# teensy_robotica.net
KiCad netlist of a schematic drawn in EAGLE
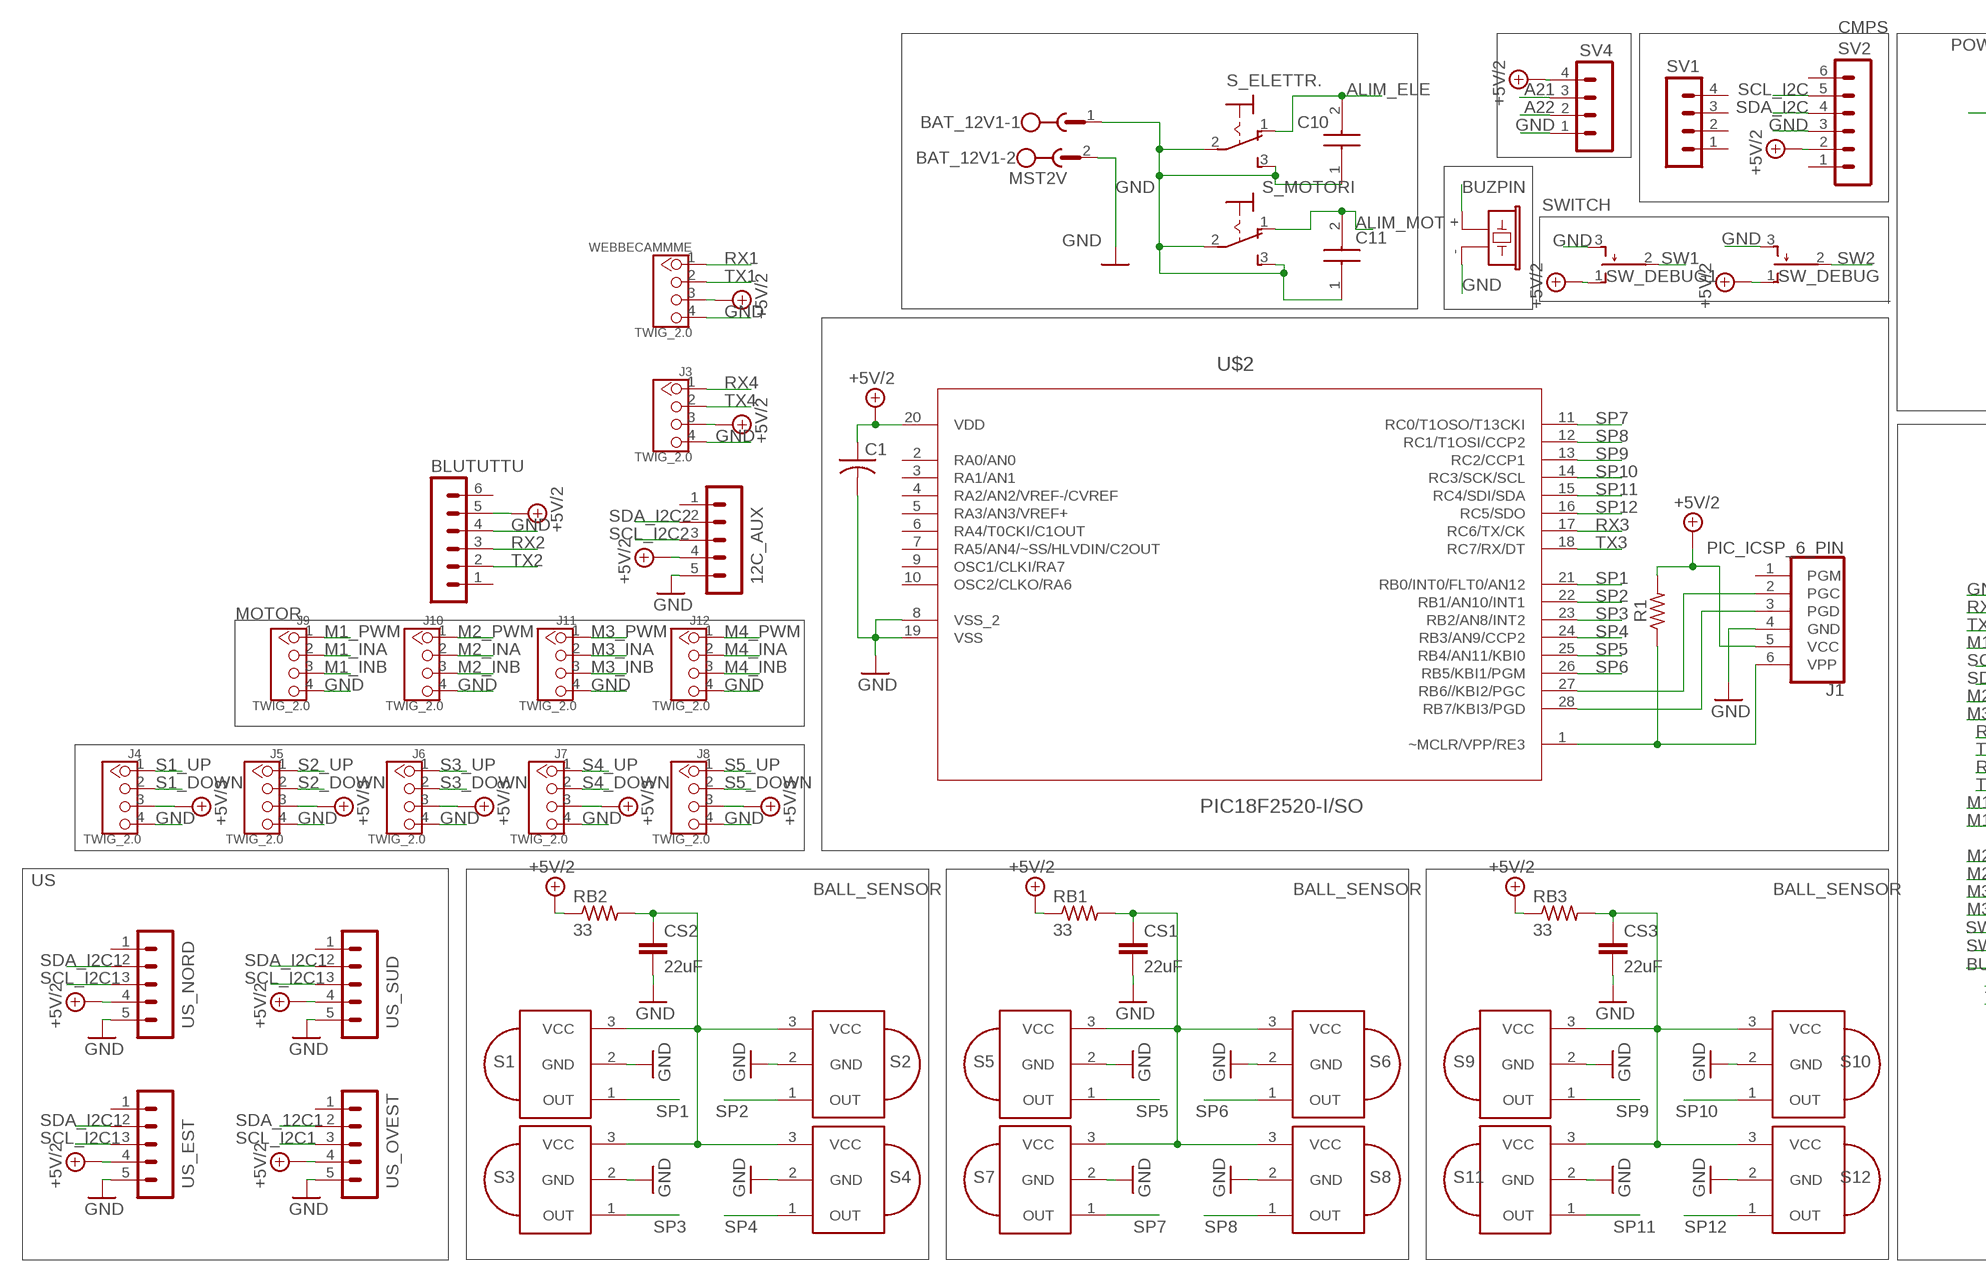
[diagram p0: schematic, sheet 1, part 1 of 2]
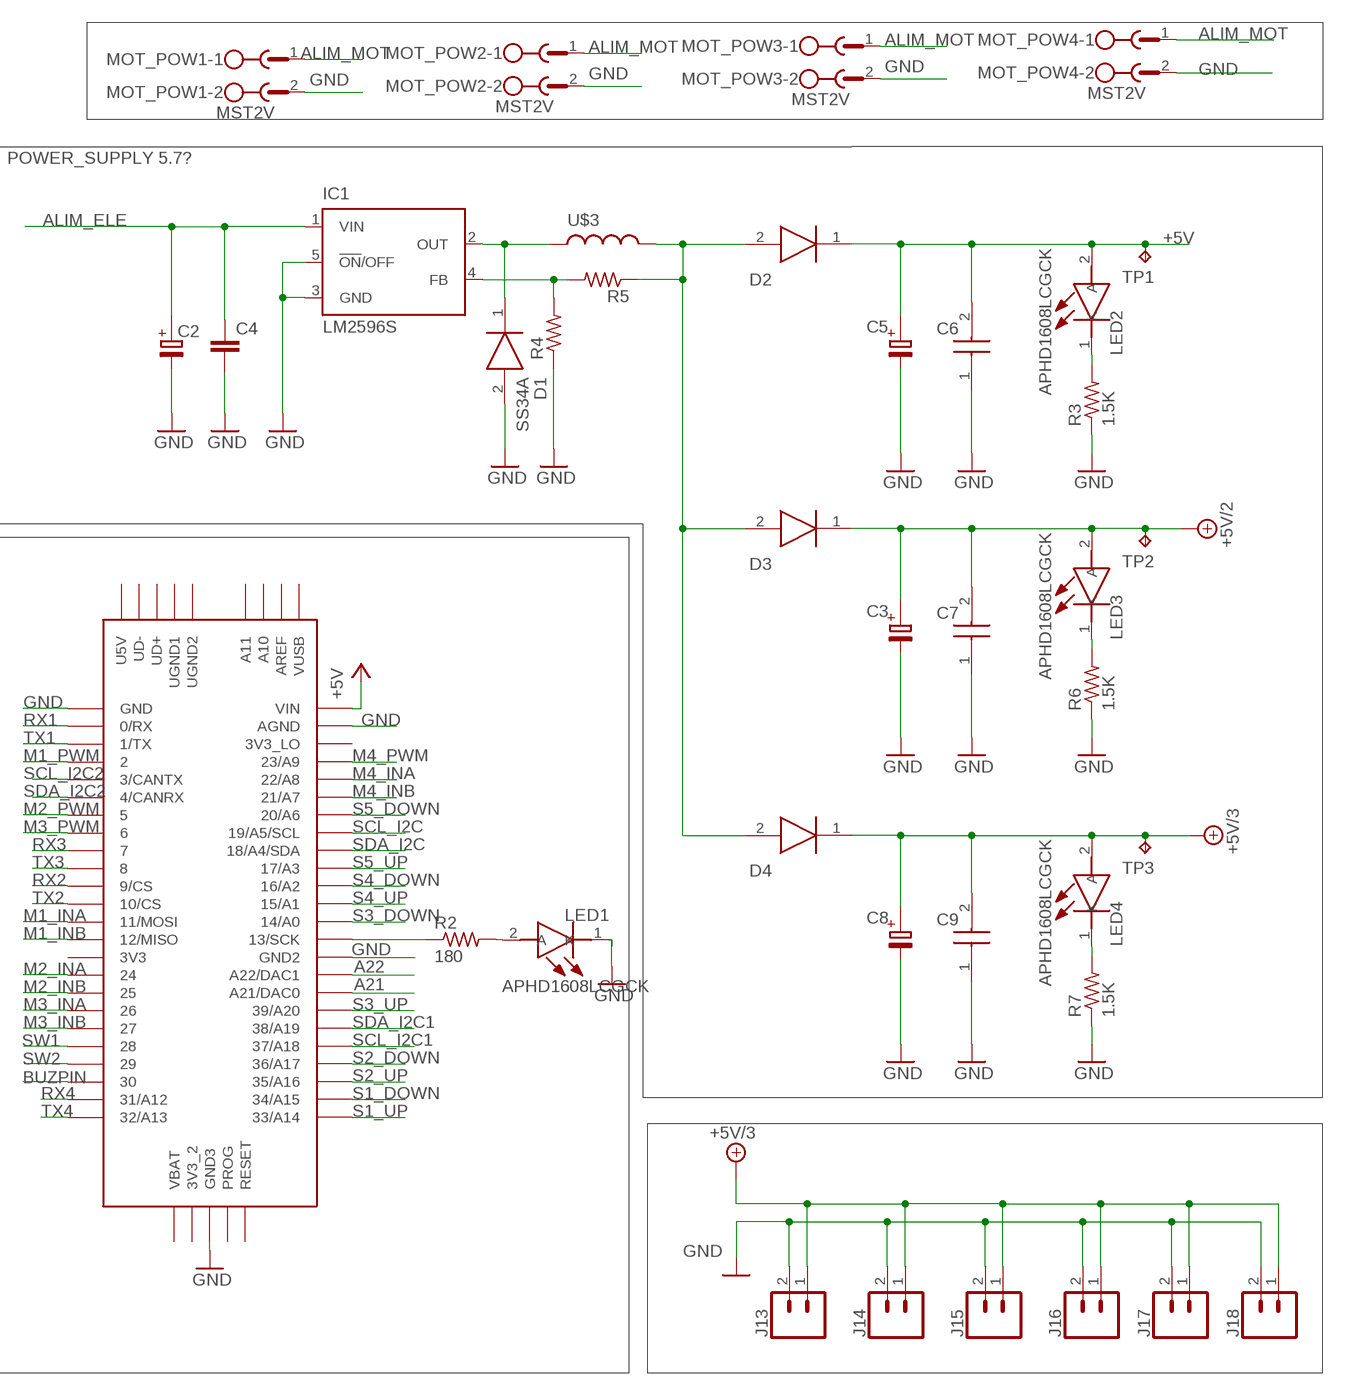
[diagram p1: schematic, sheet 1, part 2 of 2]

(export (version "E")
  (design (tool "Eeschema 10.0.6"))
  (components
    (comp (ref "12C_AUX")
      (value "MA05-1")
      (footprint "eagle-import:MA05-1")
      (libsource (lib "eagle-import") (part "MA05-1"))
    )
    (comp (ref "BAT_12V1")
      (value "MST2V")
      (footprint "eagle-import:MSTBV2")
      (libsource (lib "eagle-import") (part "MST2V"))
    )
    (comp (ref "BLUTUTTU")
      (value "MA06-1")
      (footprint "eagle-import:MA06-1")
      (libsource (lib "eagle-import") (part "MA06-1"))
    )
    (comp (ref "C1")
      (value "C-USC1206")
      (footprint "eagle-import:C1206")
      (libsource (lib "eagle-import") (part "C-USC1206"))
    )
    (comp (ref "C2")
      (value "C-PR-SMD-SV-E/F")
      (footprint "eagle-import:SV-E_F")
      (libsource (lib "eagle-import") (part "C-PR-SMD-SV-E/F"))
    )
    (comp (ref "C3")
      (value "C-PR-SMD-SV-E/F")
      (footprint "eagle-import:SV-E_F")
      (libsource (lib "eagle-import") (part "C-PR-SMD-SV-E/F"))
    )
    (comp (ref "C4")
      (value "CC1206")
      (footprint "eagle-import:C1206")
      (libsource (lib "eagle-import") (part "CC1206"))
    )
    (comp (ref "C5")
      (value "C-PR-SMD-SV-E/F")
      (footprint "eagle-import:SV-E_F")
      (libsource (lib "eagle-import") (part "C-PR-SMD-SV-E/F"))
    )
    (comp (ref "C6")
      (value "12065D106KAT2A")
      (footprint "eagle-import:CAPC3216X229N")
      (libsource (lib "eagle-import") (part "12065D106KAT2A"))
    )
    (comp (ref "C7")
      (value "12065D106KAT2A")
      (footprint "eagle-import:CAPC3216X229N")
      (libsource (lib "eagle-import") (part "12065D106KAT2A"))
    )
    (comp (ref "C8")
      (value "C-PR-SMD-SV-E/F")
      (footprint "eagle-import:SV-E_F")
      (libsource (lib "eagle-import") (part "C-PR-SMD-SV-E/F"))
    )
    (comp (ref "C9")
      (value "12065D106KAT2A")
      (footprint "eagle-import:CAPC3216X229N")
      (libsource (lib "eagle-import") (part "12065D106KAT2A"))
    )
    (comp (ref "C10")
      (value "12065D106KAT2A")
      (footprint "eagle-import:CAPC3216X229N")
      (libsource (lib "eagle-import") (part "12065D106KAT2A"))
    )
    (comp (ref "C11")
      (value "12065D106KAT2A")
      (footprint "eagle-import:CAPC3216X229N")
      (libsource (lib "eagle-import") (part "12065D106KAT2A"))
    )
    (comp (ref "CS1")
      (value "22uF")
      (footprint "eagle-import:C1206")
      (libsource (lib "eagle-import") (part "C-EUC1206"))
    )
    (comp (ref "CS2")
      (value "22uF")
      (footprint "eagle-import:C1206")
      (libsource (lib "eagle-import") (part "C-EUC1206"))
    )
    (comp (ref "CS3")
      (value "22uF")
      (footprint "eagle-import:C1206")
      (libsource (lib "eagle-import") (part "C-EUC1206"))
    )
    (comp (ref "D1")
      (value "SS34A")
      (footprint "eagle-import:DIOM5026X262N")
      (fields (field (name "RS_PART_NUMBER") "1711454"))
      (libsource (lib "eagle-import") (part "SS34A"))
    )
    (comp (ref "D2")
      (value "SE20FG-M3_H")
      (footprint "eagle-import:SODFL3718X108N")
      (fields
        (field (name "MANUFACTURER_PART_NUMBER") "SE20FG-M3/H")
        (field (name "RS_PART_NUMBER") "8949262P")
      )
      (libsource (lib "eagle-import") (part "SE20FG-M3_H"))
    )
    (comp (ref "D3")
      (value "SE20FG-M3_H")
      (footprint "eagle-import:SODFL3718X108N")
      (fields
        (field (name "MANUFACTURER_PART_NUMBER") "SE20FG-M3/H")
        (field (name "RS_PART_NUMBER") "8949262P")
      )
      (libsource (lib "eagle-import") (part "SE20FG-M3_H"))
    )
    (comp (ref "D4")
      (value "SE20FG-M3_H")
      (footprint "eagle-import:SODFL3718X108N")
      (fields
        (field (name "MANUFACTURER_PART_NUMBER") "SE20FG-M3/H")
        (field (name "RS_PART_NUMBER") "8949262P")
      )
      (libsource (lib "eagle-import") (part "SE20FG-M3_H"))
    )
    (comp (ref "IC1")
      (value "LM2596S")
      (footprint "eagle-import:TO263-5")
      (fields (field (name "MF") "NATIONAL SEMICONDUCTOR") (field (name "MPN") "LM2596S-ADJ/NOPB"))
      (libsource (lib "eagle-import") (part "LM2596S"))
    )
    (comp (ref "J1")
      (value "PIC_ICSP_6_PIN")
      (footprint "eagle-import:MOLEX-1X6")
      (libsource (lib "eagle-import") (part "PIC_ICSP_6_PIN"))
    )
    (comp (ref "J3")
      (value "TWIG_2.0")
      (footprint "eagle-import:2.0_1X4")
      (libsource (lib "eagle-import") (part "TWIG_2.0"))
    )
    (comp (ref "J4")
      (value "TWIG_2.0")
      (footprint "eagle-import:2.0_1X4")
      (libsource (lib "eagle-import") (part "TWIG_2.0"))
    )
    (comp (ref "J5")
      (value "TWIG_2.0")
      (footprint "eagle-import:2.0_1X4")
      (libsource (lib "eagle-import") (part "TWIG_2.0"))
    )
    (comp (ref "J6")
      (value "TWIG_2.0")
      (footprint "eagle-import:2.0_1X4")
      (libsource (lib "eagle-import") (part "TWIG_2.0"))
    )
    (comp (ref "J7")
      (value "TWIG_2.0")
      (footprint "eagle-import:2.0_1X4")
      (libsource (lib "eagle-import") (part "TWIG_2.0"))
    )
    (comp (ref "J8")
      (value "TWIG_2.0")
      (footprint "eagle-import:2.0_1X4")
      (libsource (lib "eagle-import") (part "TWIG_2.0"))
    )
    (comp (ref "J9")
      (value "TWIG_2.0")
      (footprint "eagle-import:2.0_1X4")
      (libsource (lib "eagle-import") (part "TWIG_2.0"))
    )
    (comp (ref "J10")
      (value "TWIG_2.0")
      (footprint "eagle-import:2.0_1X4")
      (libsource (lib "eagle-import") (part "TWIG_2.0"))
    )
    (comp (ref "J11")
      (value "TWIG_2.0")
      (footprint "eagle-import:2.0_1X4")
      (libsource (lib "eagle-import") (part "TWIG_2.0"))
    )
    (comp (ref "J12")
      (value "TWIG_2.0")
      (footprint "eagle-import:2.0_1X4")
      (libsource (lib "eagle-import") (part "TWIG_2.0"))
    )
    (comp (ref "J13")
      (value "CONN_02")
      (footprint "eagle-import:1X02")
      (libsource (lib "eagle-import") (part "CONN_02"))
    )
    (comp (ref "J14")
      (value "CONN_02")
      (footprint "eagle-import:1X02")
      (libsource (lib "eagle-import") (part "CONN_02"))
    )
    (comp (ref "J15")
      (value "CONN_02")
      (footprint "eagle-import:1X02")
      (libsource (lib "eagle-import") (part "CONN_02"))
    )
    (comp (ref "J16")
      (value "CONN_02")
      (footprint "eagle-import:1X02")
      (libsource (lib "eagle-import") (part "CONN_02"))
    )
    (comp (ref "J17")
      (value "CONN_02")
      (footprint "eagle-import:1X02")
      (libsource (lib "eagle-import") (part "CONN_02"))
    )
    (comp (ref "J18")
      (value "CONN_02")
      (footprint "eagle-import:1X02")
      (libsource (lib "eagle-import") (part "CONN_02"))
    )
    (comp (ref "LED1")
      (value "APHD1608LCGCK")
      (footprint "eagle-import:LEDM168X80N")
      (fields (field (name "MOUSER_PART_NUMBER") "604-APHD1608LCGCK"))
      (libsource (lib "eagle-import") (part "APHD1608LCGCK"))
    )
    (comp (ref "LED2")
      (value "APHD1608LCGCK")
      (footprint "eagle-import:LEDM168X80N")
      (fields (field (name "MOUSER_PART_NUMBER") "604-APHD1608LCGCK"))
      (libsource (lib "eagle-import") (part "APHD1608LCGCK"))
    )
    (comp (ref "LED3")
      (value "APHD1608LCGCK")
      (footprint "eagle-import:LEDM168X80N")
      (fields (field (name "MOUSER_PART_NUMBER") "604-APHD1608LCGCK"))
      (libsource (lib "eagle-import") (part "APHD1608LCGCK"))
    )
    (comp (ref "LED4")
      (value "APHD1608LCGCK")
      (footprint "eagle-import:LEDM168X80N")
      (fields (field (name "MOUSER_PART_NUMBER") "604-APHD1608LCGCK"))
      (libsource (lib "eagle-import") (part "APHD1608LCGCK"))
    )
    (comp (ref "MOT_POW1")
      (value "MST2V")
      (footprint "eagle-import:MSTBV2")
      (libsource (lib "eagle-import") (part "MST2V"))
    )
    (comp (ref "MOT_POW2")
      (value "MST2V")
      (footprint "eagle-import:MSTBV2")
      (libsource (lib "eagle-import") (part "MST2V"))
    )
    (comp (ref "MOT_POW3")
      (value "MST2V")
      (footprint "eagle-import:MSTBV2")
      (libsource (lib "eagle-import") (part "MST2V"))
    )
    (comp (ref "MOT_POW4")
      (value "MST2V")
      (footprint "eagle-import:MSTBV2")
      (libsource (lib "eagle-import") (part "MST2V"))
    )
    (comp (ref "R1")
      (value "10k")
      (footprint "eagle-import:M1206")
      (libsource (lib "eagle-import") (part "R-US_M1206"))
    )
    (comp (ref "R2")
      (value "180")
      (footprint "eagle-import:M1206")
      (libsource (lib "eagle-import") (part "R-US_M1206"))
    )
    (comp (ref "R3")
      (value "1.5K")
      (footprint "eagle-import:R1206")
      (libsource (lib "eagle-import") (part "R-US_R1206"))
    )
    (comp (ref "R4")
      (value "R-US_R1206")
      (footprint "eagle-import:R1206")
      (libsource (lib "eagle-import") (part "R-US_R1206"))
    )
    (comp (ref "R5")
      (value "R-US_R1206")
      (footprint "eagle-import:R1206")
      (libsource (lib "eagle-import") (part "R-US_R1206"))
    )
    (comp (ref "R6")
      (value "1.5K")
      (footprint "eagle-import:R1206")
      (libsource (lib "eagle-import") (part "R-US_R1206"))
    )
    (comp (ref "R7")
      (value "1.5K")
      (footprint "eagle-import:R1206")
      (libsource (lib "eagle-import") (part "R-US_R1206"))
    )
    (comp (ref "RB1")
      (value "33")
      (footprint "eagle-import:M1206")
      (libsource (lib "eagle-import") (part "R-US_M1206"))
    )
    (comp (ref "RB2")
      (value "33")
      (footprint "eagle-import:M1206")
      (libsource (lib "eagle-import") (part "R-US_M1206"))
    )
    (comp (ref "RB3")
      (value "33")
      (footprint "eagle-import:M1206")
      (libsource (lib "eagle-import") (part "R-US_M1206"))
    )
    (comp (ref "S1")
      (value "PNA460XM")
      (footprint "eagle-import:PNA460XM")
      (libsource (lib "eagle-import") (part "PNA460XM"))
    )
    (comp (ref "S2")
      (value "PNA460XM")
      (footprint "eagle-import:PNA460XM")
      (libsource (lib "eagle-import") (part "PNA460XM"))
    )
    (comp (ref "S3")
      (value "PNA460XM")
      (footprint "eagle-import:PNA460XM")
      (libsource (lib "eagle-import") (part "PNA460XM"))
    )
    (comp (ref "S4")
      (value "PNA460XM")
      (footprint "eagle-import:PNA460XM")
      (libsource (lib "eagle-import") (part "PNA460XM"))
    )
    (comp (ref "S5")
      (value "PNA460XM")
      (footprint "eagle-import:PNA460XM")
      (libsource (lib "eagle-import") (part "PNA460XM"))
    )
    (comp (ref "S6")
      (value "PNA460XM")
      (footprint "eagle-import:PNA460XM")
      (libsource (lib "eagle-import") (part "PNA460XM"))
    )
    (comp (ref "S7")
      (value "PNA460XM")
      (footprint "eagle-import:PNA460XM")
      (libsource (lib "eagle-import") (part "PNA460XM"))
    )
    (comp (ref "S8")
      (value "PNA460XM")
      (footprint "eagle-import:PNA460XM")
      (libsource (lib "eagle-import") (part "PNA460XM"))
    )
    (comp (ref "S9")
      (value "PNA460XM")
      (footprint "eagle-import:PNA460XM")
      (libsource (lib "eagle-import") (part "PNA460XM"))
    )
    (comp (ref "S10")
      (value "PNA460XM")
      (footprint "eagle-import:PNA460XM")
      (libsource (lib "eagle-import") (part "PNA460XM"))
    )
    (comp (ref "S11")
      (value "PNA460XM")
      (footprint "eagle-import:PNA460XM")
      (libsource (lib "eagle-import") (part "PNA460XM"))
    )
    (comp (ref "S12")
      (value "PNA460XM")
      (footprint "eagle-import:PNA460XM")
      (libsource (lib "eagle-import") (part "PNA460XM"))
    )
    (comp (ref "SG1")
      (value "F/CM12P")
      (footprint "eagle-import:F_CM12P")
      (libsource (lib "eagle-import") (part "F/CM12P"))
    )
    (comp (ref "SV1")
      (value "MA04-1")
      (footprint "eagle-import:MA04-1")
      (libsource (lib "eagle-import") (part "MA04-1"))
    )
    (comp (ref "SV2")
      (value "MA06-1")
      (footprint "eagle-import:MA06-1")
      (libsource (lib "eagle-import") (part "MA06-1"))
    )
    (comp (ref "SV4")
      (value "MA04-1")
      (footprint "eagle-import:MA04-1")
      (libsource (lib "eagle-import") (part "MA04-1"))
    )
    (comp (ref "SW_DEBUG")
      (value "TL38PO")
      (footprint "eagle-import:TL3XPO")
      (libsource (lib "eagle-import") (part "TL38PO"))
    )
    (comp (ref "SW_DEBUG1")
      (value "TL38PO")
      (footprint "eagle-import:TL3XPO")
      (libsource (lib "eagle-import") (part "TL38PO"))
    )
    (comp (ref "S_ELETTR.")
      (value "320-916")
      (footprint "eagle-import:320-916")
      (libsource (lib "eagle-import") (part "320-916"))
    )
    (comp (ref "S_MOTORI")
      (value "320-916")
      (footprint "eagle-import:320-916")
      (libsource (lib "eagle-import") (part "320-916"))
    )
    (comp (ref "TP1")
      (value "TPTP13SQ")
      (footprint "eagle-import:TP13SQ")
      (libsource (lib "eagle-import") (part "TPTP13SQ"))
    )
    (comp (ref "TP2")
      (value "TPTP13SQ")
      (footprint "eagle-import:TP13SQ")
      (libsource (lib "eagle-import") (part "TPTP13SQ"))
    )
    (comp (ref "TP3")
      (value "TPTP13SQ")
      (footprint "eagle-import:TP13SQ")
      (libsource (lib "eagle-import") (part "TPTP13SQ"))
    )
    (comp (ref "U$1")
      (value "TEENSY_3.5/3.6")
      (footprint "eagle-import:TEENSY_3.5_3.6")
      (libsource (lib "eagle-import") (part "TEENSY_3.5/3.6"))
    )
    (comp (ref "U$2")
      (value "PIC18F2520-I/SO")
      (footprint "eagle-import:SOIC127P1030X265-28N")
      (libsource (lib "eagle-import") (part "PIC18F2520-I/SO"))
    )
    (comp (ref "U$3")
      (value "MSS1260")
      (footprint "eagle-import:MSS1260")
      (libsource (lib "eagle-import") (part "MSS1260"))
    )
    (comp (ref "US_EST")
      (value "MA05-1")
      (footprint "eagle-import:MA05-1")
      (libsource (lib "eagle-import") (part "MA05-1"))
    )
    (comp (ref "US_NORD")
      (value "MA05-1")
      (footprint "eagle-import:MA05-1")
      (libsource (lib "eagle-import") (part "MA05-1"))
    )
    (comp (ref "US_OVEST")
      (value "MA05-1")
      (footprint "eagle-import:MA05-1")
      (libsource (lib "eagle-import") (part "MA05-1"))
    )
    (comp (ref "US_SUD")
      (value "MA05-1")
      (footprint "eagle-import:MA05-1")
      (libsource (lib "eagle-import") (part "MA05-1"))
    )
    (comp (ref "WEBBECAMMME")
      (value "TWIG_2.0")
      (footprint "eagle-import:2.0_1X4")
      (libsource (lib "eagle-import") (part "TWIG_2.0"))
    )
  )
  (nets
    (net (code "1") (name "+5V") (class "Default")
      (node (ref "C5") (pin "+") (pinfunction "+_+") (pintype "passive"))
      (node (ref "C6") (pin "2") (pinfunction "2_2") (pintype "bidirectional"))
      (node (ref "D2") (pin "1") (pinfunction "K_1") (pintype "bidirectional"))
      (node (ref "LED2") (pin "2") (pinfunction "A_2") (pintype "bidirectional"))
      (node (ref "TP1") (pin "TP") (pinfunction "TP_TP") (pintype "input"))
      (node (ref "U$1") (pin "VIN") (pinfunction "VIN_VIN") (pintype "bidirectional"))
    )
    (net (code "2") (name "+5V{slash}2") (class "Default")
      (node (ref "12C_AUX") (pin "4") (pinfunction "4_4") (pintype "passive"))
      (node (ref "BLUTUTTU") (pin "5") (pinfunction "5_5") (pintype "passive"))
      (node (ref "C1") (pin "1") (pinfunction "1_1") (pintype "passive"))
      (node (ref "C3") (pin "+") (pinfunction "+_+") (pintype "passive"))
      (node (ref "C7") (pin "2") (pinfunction "2_2") (pintype "bidirectional"))
      (node (ref "D3") (pin "1") (pinfunction "K_1") (pintype "bidirectional"))
      (node (ref "J1") (pin "5") (pinfunction "VCC_5") (pintype "power_in"))
      (node (ref "J3") (pin "3") (pinfunction "3_3") (pintype "bidirectional"))
      (node (ref "LED3") (pin "2") (pinfunction "A_2") (pintype "bidirectional"))
      (node (ref "R1") (pin "2") (pinfunction "2_2") (pintype "passive"))
      (node (ref "RB1") (pin "1") (pinfunction "1_1") (pintype "passive"))
      (node (ref "RB2") (pin "1") (pinfunction "1_1") (pintype "passive"))
      (node (ref "RB3") (pin "1") (pinfunction "1_1") (pintype "passive"))
      (node (ref "SV2") (pin "2") (pinfunction "2_2") (pintype "passive"))
      (node (ref "SV4") (pin "4") (pinfunction "4_4") (pintype "passive"))
      (node (ref "SW_DEBUG") (pin "1") (pinfunction "O_1") (pintype "passive"))
      (node (ref "SW_DEBUG1") (pin "1") (pinfunction "O_1") (pintype "passive"))
      (node (ref "TP2") (pin "TP") (pinfunction "TP_TP") (pintype "input"))
      (node (ref "U$2") (pin "20") (pinfunction "VDD_20") (pintype "bidirectional"))
      (node (ref "US_EST") (pin "4") (pinfunction "4_4") (pintype "passive"))
      (node (ref "US_NORD") (pin "4") (pinfunction "4_4") (pintype "passive"))
      (node (ref "US_OVEST") (pin "4") (pinfunction "4_4") (pintype "passive"))
      (node (ref "US_SUD") (pin "4") (pinfunction "4_4") (pintype "passive"))
      (node (ref "WEBBECAMMME") (pin "3") (pinfunction "3_3") (pintype "bidirectional"))
    )
    (net (code "3") (name "+5V{slash}3") (class "Default")
      (node (ref "C8") (pin "+") (pinfunction "+_+") (pintype "passive"))
      (node (ref "C9") (pin "2") (pinfunction "2_2") (pintype "bidirectional"))
      (node (ref "D4") (pin "1") (pinfunction "K_1") (pintype "bidirectional"))
      (node (ref "J13") (pin "1") (pinfunction "1_1") (pintype "passive"))
      (node (ref "J14") (pin "1") (pinfunction "1_1") (pintype "passive"))
      (node (ref "J15") (pin "1") (pinfunction "1_1") (pintype "passive"))
      (node (ref "J16") (pin "1") (pinfunction "1_1") (pintype "passive"))
      (node (ref "J17") (pin "1") (pinfunction "1_1") (pintype "passive"))
      (node (ref "J18") (pin "1") (pinfunction "1_1") (pintype "passive"))
      (node (ref "J4") (pin "3") (pinfunction "3_3") (pintype "bidirectional"))
      (node (ref "J5") (pin "3") (pinfunction "3_3") (pintype "bidirectional"))
      (node (ref "J6") (pin "3") (pinfunction "3_3") (pintype "bidirectional"))
      (node (ref "J7") (pin "3") (pinfunction "3_3") (pintype "bidirectional"))
      (node (ref "J8") (pin "3") (pinfunction "3_3") (pintype "bidirectional"))
      (node (ref "LED4") (pin "2") (pinfunction "A_2") (pintype "bidirectional"))
      (node (ref "TP3") (pin "TP") (pinfunction "TP_TP") (pintype "input"))
    )
    (net (code "4") (name "/A21") (class "Default")
      (node (ref "SV4") (pin "3") (pinfunction "3_3") (pintype "passive"))
      (node (ref "U$1") (pin "21/DAC0") (pinfunction "A21/DAC0_21/DAC0") (pintype "bidirectional"))
    )
    (net (code "5") (name "/A22") (class "Default")
      (node (ref "SV4") (pin "2") (pinfunction "2_2") (pintype "passive"))
      (node (ref "U$1") (pin "A22/DAC1") (pinfunction "A22/DAC1_A22/DAC1") (pintype "bidirectional"))
    )
    (net (code "6") (name "/ALIM_ELE") (class "Default")
      (node (ref "C10") (pin "2") (pinfunction "2_2") (pintype "bidirectional"))
      (node (ref "C2") (pin "+") (pinfunction "+_+") (pintype "passive"))
      (node (ref "C4") (pin "1") (pinfunction "1_1") (pintype "passive"))
      (node (ref "IC1") (pin "1") (pinfunction "VIN_1") (pintype "input"))
      (node (ref "S_ELETTR.") (pin "1") (pinfunction "O_1") (pintype "passive"))
    )
    (net (code "7") (name "/ALIM_MOT") (class "Default")
      (node (ref "C11") (pin "2") (pinfunction "2_2") (pintype "bidirectional"))
      (node (ref "MOT_POW1") (pin "1") (pinfunction "1_1") (pintype "passive"))
      (node (ref "MOT_POW2") (pin "1") (pinfunction "1_1") (pintype "passive"))
      (node (ref "MOT_POW3") (pin "1") (pinfunction "1_1") (pintype "passive"))
      (node (ref "MOT_POW4") (pin "1") (pinfunction "1_1") (pintype "passive"))
      (node (ref "S_MOTORI") (pin "1") (pinfunction "O_1") (pintype "passive"))
    )
    (net (code "8") (name "/BUZPIN") (class "Default")
      (node (ref "SG1") (pin "+") (pinfunction "1_+") (pintype "passive"))
      (node (ref "U$1") (pin "30") (pinfunction "30_30") (pintype "bidirectional"))
    )
    (net (code "9") (name "/M1_INA") (class "Default")
      (node (ref "J9") (pin "2") (pinfunction "2_2") (pintype "bidirectional"))
      (node (ref "U$1") (pin "11/MOSI") (pinfunction "11/MOSI_11/MOSI") (pintype "bidirectional"))
    )
    (net (code "10") (name "/M1_INB") (class "Default")
      (node (ref "J9") (pin "3") (pinfunction "3_3") (pintype "bidirectional"))
      (node (ref "U$1") (pin "12/MISO") (pinfunction "12/MISO_12/MISO") (pintype "bidirectional"))
    )
    (net (code "11") (name "/M1_PWM") (class "Default")
      (node (ref "J9") (pin "1") (pinfunction "1_1") (pintype "bidirectional"))
      (node (ref "U$1") (pin "2") (pinfunction "2_2") (pintype "bidirectional"))
    )
    (net (code "12") (name "/M2_INA") (class "Default")
      (node (ref "J10") (pin "2") (pinfunction "2_2") (pintype "bidirectional"))
      (node (ref "U$1") (pin "24") (pinfunction "24_24") (pintype "bidirectional"))
    )
    (net (code "13") (name "/M2_INB") (class "Default")
      (node (ref "J10") (pin "3") (pinfunction "3_3") (pintype "bidirectional"))
      (node (ref "U$1") (pin "25") (pinfunction "25_25") (pintype "bidirectional"))
    )
    (net (code "14") (name "/M2_PWM") (class "Default")
      (node (ref "J10") (pin "1") (pinfunction "1_1") (pintype "bidirectional"))
      (node (ref "U$1") (pin "5") (pinfunction "5_5") (pintype "bidirectional"))
    )
    (net (code "15") (name "/M3_INA") (class "Default")
      (node (ref "J11") (pin "2") (pinfunction "2_2") (pintype "bidirectional"))
      (node (ref "U$1") (pin "26") (pinfunction "26_26") (pintype "bidirectional"))
    )
    (net (code "16") (name "/M3_INB") (class "Default")
      (node (ref "J11") (pin "3") (pinfunction "3_3") (pintype "bidirectional"))
      (node (ref "U$1") (pin "27") (pinfunction "27_27") (pintype "bidirectional"))
    )
    (net (code "17") (name "/M3_PWM") (class "Default")
      (node (ref "J11") (pin "1") (pinfunction "1_1") (pintype "bidirectional"))
      (node (ref "U$1") (pin "6") (pinfunction "6_6") (pintype "bidirectional"))
    )
    (net (code "18") (name "/M4_INA") (class "Default")
      (node (ref "J12") (pin "2") (pinfunction "2_2") (pintype "bidirectional"))
      (node (ref "U$1") (pin "22/A8") (pinfunction "22/A8_22/A8") (pintype "bidirectional"))
    )
    (net (code "19") (name "/M4_INB") (class "Default")
      (node (ref "J12") (pin "3") (pinfunction "3_3") (pintype "bidirectional"))
      (node (ref "U$1") (pin "21/A7") (pinfunction "21/A7_21/A7") (pintype "bidirectional"))
    )
    (net (code "20") (name "/M4_PWM") (class "Default")
      (node (ref "J12") (pin "1") (pinfunction "1_1") (pintype "bidirectional"))
      (node (ref "U$1") (pin "23/A9") (pinfunction "23/A9_23/A9") (pintype "bidirectional"))
    )
    (net (code "21") (name "/RX1") (class "Default")
      (node (ref "U$1") (pin "0/RX") (pinfunction "0/RX_0/RX") (pintype "bidirectional"))
      (node (ref "WEBBECAMMME") (pin "1") (pinfunction "1_1") (pintype "bidirectional"))
    )
    (net (code "22") (name "/RX2") (class "Default")
      (node (ref "BLUTUTTU") (pin "3") (pinfunction "3_3") (pintype "passive"))
      (node (ref "U$1") (pin "9/CS") (pinfunction "9/CS_9/CS") (pintype "bidirectional"))
    )
    (net (code "23") (name "/RX3") (class "Default")
      (node (ref "U$1") (pin "7") (pinfunction "7_7") (pintype "bidirectional"))
      (node (ref "U$2") (pin "17") (pinfunction "RC6/TX/CK_17") (pintype "bidirectional"))
    )
    (net (code "24") (name "/RX4") (class "Default")
      (node (ref "J3") (pin "1") (pinfunction "1_1") (pintype "bidirectional"))
      (node (ref "U$1") (pin "31/A12") (pinfunction "31/A12_31/A12") (pintype "bidirectional"))
    )
    (net (code "25") (name "/S1_DOWN") (class "Default")
      (node (ref "J4") (pin "2") (pinfunction "2_2") (pintype "bidirectional"))
      (node (ref "U$1") (pin "34/A15") (pinfunction "34/A15_34/A15") (pintype "bidirectional"))
    )
    (net (code "26") (name "/S1_UP") (class "Default")
      (node (ref "J4") (pin "1") (pinfunction "1_1") (pintype "bidirectional"))
      (node (ref "U$1") (pin "33/A14") (pinfunction "33/A14_33/A14") (pintype "bidirectional"))
    )
    (net (code "27") (name "/S2_DOWN") (class "Default")
      (node (ref "J5") (pin "2") (pinfunction "2_2") (pintype "bidirectional"))
      (node (ref "U$1") (pin "36/A17") (pinfunction "36/A17_36/A17") (pintype "bidirectional"))
    )
    (net (code "28") (name "/S2_UP") (class "Default")
      (node (ref "J5") (pin "1") (pinfunction "1_1") (pintype "bidirectional"))
      (node (ref "U$1") (pin "35/A16") (pinfunction "35/A16_35/A16") (pintype "bidirectional"))
    )
    (net (code "29") (name "/S3_DOWN") (class "Default")
      (node (ref "J6") (pin "2") (pinfunction "2_2") (pintype "bidirectional"))
      (node (ref "U$1") (pin "14/A0") (pinfunction "14/A0_14/A0") (pintype "bidirectional"))
    )
    (net (code "30") (name "/S3_UP") (class "Default")
      (node (ref "J6") (pin "1") (pinfunction "1_1") (pintype "bidirectional"))
      (node (ref "U$1") (pin "39/A20") (pinfunction "39/A20_39/A20") (pintype "bidirectional"))
    )
    (net (code "31") (name "/S4_DOWN") (class "Default")
      (node (ref "J7") (pin "2") (pinfunction "2_2") (pintype "bidirectional"))
      (node (ref "U$1") (pin "16/A2") (pinfunction "16/A2_16/A2") (pintype "bidirectional"))
    )
    (net (code "32") (name "/S4_UP") (class "Default")
      (node (ref "J7") (pin "1") (pinfunction "1_1") (pintype "bidirectional"))
      (node (ref "U$1") (pin "15/A1") (pinfunction "15/A1_15/A1") (pintype "bidirectional"))
    )
    (net (code "33") (name "/S5_DOWN") (class "Default")
      (node (ref "J8") (pin "2") (pinfunction "2_2") (pintype "bidirectional"))
      (node (ref "U$1") (pin "20/A6") (pinfunction "20/A6_20/A6") (pintype "bidirectional"))
    )
    (net (code "34") (name "/S5_UP") (class "Default")
      (node (ref "J8") (pin "1") (pinfunction "1_1") (pintype "bidirectional"))
      (node (ref "U$1") (pin "17/A3") (pinfunction "17/A3_17/A3") (pintype "bidirectional"))
    )
    (net (code "35") (name "/SCL_I2C") (class "Default")
      (node (ref "SV2") (pin "5") (pinfunction "5_5") (pintype "passive"))
      (node (ref "U$1") (pin "19/A5/SCL") (pinfunction "19/A5/SCL_19/A5/SCL") (pintype "bidirectional"))
    )
    (net (code "36") (name "/SCL_I2C1") (class "Default")
      (node (ref "U$1") (pin "37/A18") (pinfunction "37/A18_37/A18") (pintype "bidirectional"))
      (node (ref "US_EST") (pin "3") (pinfunction "3_3") (pintype "passive"))
      (node (ref "US_NORD") (pin "3") (pinfunction "3_3") (pintype "passive"))
      (node (ref "US_OVEST") (pin "3") (pinfunction "3_3") (pintype "passive"))
      (node (ref "US_SUD") (pin "3") (pinfunction "3_3") (pintype "passive"))
    )
    (net (code "37") (name "/SCL_I2C2") (class "Default")
      (node (ref "12C_AUX") (pin "3") (pinfunction "3_3") (pintype "passive"))
      (node (ref "U$1") (pin "3/CANTX") (pinfunction "3/CANTX_3/CANTX") (pintype "bidirectional"))
    )
    (net (code "38") (name "/SDA_12C1") (class "Default")
      (node (ref "US_OVEST") (pin "2") (pinfunction "2_2") (pintype "passive"))
    )
    (net (code "39") (name "/SDA_I2C") (class "Default")
      (node (ref "SV2") (pin "4") (pinfunction "4_4") (pintype "passive"))
      (node (ref "U$1") (pin "18/A4/SDA") (pinfunction "18/A4/SDA_18/A4/SDA") (pintype "bidirectional"))
    )
    (net (code "40") (name "/SDA_I2C1") (class "Default")
      (node (ref "U$1") (pin "38/A19") (pinfunction "38/A19_38/A19") (pintype "bidirectional"))
      (node (ref "US_EST") (pin "2") (pinfunction "2_2") (pintype "passive"))
      (node (ref "US_NORD") (pin "2") (pinfunction "2_2") (pintype "passive"))
      (node (ref "US_SUD") (pin "2") (pinfunction "2_2") (pintype "passive"))
    )
    (net (code "41") (name "/SDA_I2C2") (class "Default")
      (node (ref "12C_AUX") (pin "2") (pinfunction "2_2") (pintype "passive"))
      (node (ref "U$1") (pin "4/CANRX") (pinfunction "4/CANRX_4/CANRX") (pintype "bidirectional"))
    )
    (net (code "42") (name "/SP1") (class "Default")
      (node (ref "S1") (pin "1") (pinfunction "OUT_1") (pintype "output"))
      (node (ref "U$2") (pin "21") (pinfunction "RB0/INT0/FLT0/AN12_21") (pintype "bidirectional"))
    )
    (net (code "43") (name "/SP2") (class "Default")
      (node (ref "S2") (pin "1") (pinfunction "OUT_1") (pintype "output"))
      (node (ref "U$2") (pin "22") (pinfunction "RB1/AN10/INT1_22") (pintype "bidirectional"))
    )
    (net (code "44") (name "/SP3") (class "Default")
      (node (ref "S3") (pin "1") (pinfunction "OUT_1") (pintype "output"))
      (node (ref "U$2") (pin "23") (pinfunction "RB2/AN8/INT2_23") (pintype "bidirectional"))
    )
    (net (code "45") (name "/SP4") (class "Default")
      (node (ref "S4") (pin "1") (pinfunction "OUT_1") (pintype "output"))
      (node (ref "U$2") (pin "24") (pinfunction "RB3/AN9/CCP2_24") (pintype "bidirectional"))
    )
    (net (code "46") (name "/SP5") (class "Default")
      (node (ref "S5") (pin "1") (pinfunction "OUT_1") (pintype "output"))
      (node (ref "U$2") (pin "25") (pinfunction "RB4/AN11/KBI0_25") (pintype "bidirectional"))
    )
    (net (code "47") (name "/SP6") (class "Default")
      (node (ref "S6") (pin "1") (pinfunction "OUT_1") (pintype "output"))
      (node (ref "U$2") (pin "26") (pinfunction "RB5/KBI1/PGM_26") (pintype "bidirectional"))
    )
    (net (code "48") (name "/SP7") (class "Default")
      (node (ref "S7") (pin "1") (pinfunction "OUT_1") (pintype "output"))
      (node (ref "U$2") (pin "11") (pinfunction "RC0/T1OSO/T13CKI_11") (pintype "bidirectional"))
    )
    (net (code "49") (name "/SP8") (class "Default")
      (node (ref "S8") (pin "1") (pinfunction "OUT_1") (pintype "output"))
      (node (ref "U$2") (pin "12") (pinfunction "RC1/T1OSI/CCP2_12") (pintype "bidirectional"))
    )
    (net (code "50") (name "/SP9") (class "Default")
      (node (ref "S9") (pin "1") (pinfunction "OUT_1") (pintype "output"))
      (node (ref "U$2") (pin "13") (pinfunction "RC2/CCP1_13") (pintype "bidirectional"))
    )
    (net (code "51") (name "/SP10") (class "Default")
      (node (ref "S10") (pin "1") (pinfunction "OUT_1") (pintype "output"))
      (node (ref "U$2") (pin "14") (pinfunction "RC3/SCK/SCL_14") (pintype "bidirectional"))
    )
    (net (code "52") (name "/SP11") (class "Default")
      (node (ref "S11") (pin "1") (pinfunction "OUT_1") (pintype "output"))
      (node (ref "U$2") (pin "15") (pinfunction "RC4/SDI/SDA_15") (pintype "bidirectional"))
    )
    (net (code "53") (name "/SP12") (class "Default")
      (node (ref "S12") (pin "1") (pinfunction "OUT_1") (pintype "output"))
      (node (ref "U$2") (pin "16") (pinfunction "RC5/SDO_16") (pintype "bidirectional"))
    )
    (net (code "54") (name "/SW1") (class "Default")
      (node (ref "SW_DEBUG1") (pin "2") (pinfunction "P_2") (pintype "passive"))
      (node (ref "U$1") (pin "28") (pinfunction "28_28") (pintype "bidirectional"))
    )
    (net (code "55") (name "/SW2") (class "Default")
      (node (ref "SW_DEBUG") (pin "2") (pinfunction "P_2") (pintype "passive"))
      (node (ref "U$1") (pin "29") (pinfunction "29_29") (pintype "bidirectional"))
    )
    (net (code "56") (name "/TX1") (class "Default")
      (node (ref "U$1") (pin "1/TX") (pinfunction "1/TX_1/TX") (pintype "bidirectional"))
      (node (ref "WEBBECAMMME") (pin "2") (pinfunction "2_2") (pintype "bidirectional"))
    )
    (net (code "57") (name "/TX2") (class "Default")
      (node (ref "BLUTUTTU") (pin "2") (pinfunction "2_2") (pintype "passive"))
      (node (ref "U$1") (pin "10/CS") (pinfunction "10/CS_10/CS") (pintype "bidirectional"))
    )
    (net (code "58") (name "/TX3") (class "Default")
      (node (ref "U$1") (pin "8") (pinfunction "8_8") (pintype "bidirectional"))
      (node (ref "U$2") (pin "18") (pinfunction "RC7/RX/DT_18") (pintype "bidirectional"))
    )
    (net (code "59") (name "/TX4") (class "Default")
      (node (ref "J3") (pin "2") (pinfunction "2_2") (pintype "bidirectional"))
      (node (ref "U$1") (pin "32/A13") (pinfunction "32/A13_32/A13") (pintype "bidirectional"))
    )
    (net (code "60") (name "GND") (class "Default")
      (node (ref "12C_AUX") (pin "5") (pinfunction "5_5") (pintype "passive"))
      (node (ref "BAT_12V1") (pin "2") (pinfunction "1_2") (pintype "passive"))
      (node (ref "BLUTUTTU") (pin "4") (pinfunction "4_4") (pintype "passive"))
      (node (ref "C1") (pin "2") (pinfunction "2_2") (pintype "passive"))
      (node (ref "C2") (pin "-") (pinfunction "-_-") (pintype "passive"))
      (node (ref "C3") (pin "-") (pinfunction "-_-") (pintype "passive"))
      (node (ref "C4") (pin "2") (pinfunction "2_2") (pintype "passive"))
      (node (ref "C5") (pin "-") (pinfunction "-_-") (pintype "passive"))
      (node (ref "C6") (pin "1") (pinfunction "1_1") (pintype "bidirectional"))
      (node (ref "C7") (pin "1") (pinfunction "1_1") (pintype "bidirectional"))
      (node (ref "C8") (pin "-") (pinfunction "-_-") (pintype "passive"))
      (node (ref "C9") (pin "1") (pinfunction "1_1") (pintype "bidirectional"))
      (node (ref "CS1") (pin "2") (pinfunction "2_2") (pintype "passive"))
      (node (ref "CS2") (pin "2") (pinfunction "2_2") (pintype "passive"))
      (node (ref "CS3") (pin "2") (pinfunction "2_2") (pintype "passive"))
      (node (ref "D1") (pin "2") (pinfunction "A_2") (pintype "bidirectional"))
      (node (ref "IC1") (pin "3") (pinfunction "GND_3") (pintype "power_in"))
      (node (ref "IC1") (pin "5") (pinfunction "~{ON}/OFF_5") (pintype "input"))
      (node (ref "J1") (pin "4") (pinfunction "GND_4") (pintype "power_in"))
      (node (ref "J10") (pin "4") (pinfunction "4_4") (pintype "bidirectional"))
      (node (ref "J11") (pin "4") (pinfunction "4_4") (pintype "bidirectional"))
      (node (ref "J12") (pin "4") (pinfunction "4_4") (pintype "bidirectional"))
      (node (ref "J13") (pin "2") (pinfunction "2_2") (pintype "passive"))
      (node (ref "J14") (pin "2") (pinfunction "2_2") (pintype "passive"))
      (node (ref "J15") (pin "2") (pinfunction "2_2") (pintype "passive"))
      (node (ref "J16") (pin "2") (pinfunction "2_2") (pintype "passive"))
      (node (ref "J17") (pin "2") (pinfunction "2_2") (pintype "passive"))
      (node (ref "J18") (pin "2") (pinfunction "2_2") (pintype "passive"))
      (node (ref "J3") (pin "4") (pinfunction "4_4") (pintype "bidirectional"))
      (node (ref "J4") (pin "4") (pinfunction "4_4") (pintype "bidirectional"))
      (node (ref "J5") (pin "4") (pinfunction "4_4") (pintype "bidirectional"))
      (node (ref "J6") (pin "4") (pinfunction "4_4") (pintype "bidirectional"))
      (node (ref "J7") (pin "4") (pinfunction "4_4") (pintype "bidirectional"))
      (node (ref "J8") (pin "4") (pinfunction "4_4") (pintype "bidirectional"))
      (node (ref "J9") (pin "4") (pinfunction "4_4") (pintype "bidirectional"))
      (node (ref "LED1") (pin "1") (pinfunction "K_1") (pintype "bidirectional"))
      (node (ref "MOT_POW1") (pin "2") (pinfunction "1_2") (pintype "passive"))
      (node (ref "MOT_POW2") (pin "2") (pinfunction "1_2") (pintype "passive"))
      (node (ref "MOT_POW3") (pin "2") (pinfunction "1_2") (pintype "passive"))
      (node (ref "MOT_POW4") (pin "2") (pinfunction "1_2") (pintype "passive"))
      (node (ref "R3") (pin "1") (pinfunction "1_1") (pintype "passive"))
      (node (ref "R4") (pin "1") (pinfunction "1_1") (pintype "passive"))
      (node (ref "R6") (pin "1") (pinfunction "1_1") (pintype "passive"))
      (node (ref "R7") (pin "1") (pinfunction "1_1") (pintype "passive"))
      (node (ref "S1") (pin "2") (pinfunction "GND_2") (pintype "power_in"))
      (node (ref "S10") (pin "2") (pinfunction "GND_2") (pintype "power_in"))
      (node (ref "S11") (pin "2") (pinfunction "GND_2") (pintype "power_in"))
      (node (ref "S12") (pin "2") (pinfunction "GND_2") (pintype "power_in"))
      (node (ref "S2") (pin "2") (pinfunction "GND_2") (pintype "power_in"))
      (node (ref "S3") (pin "2") (pinfunction "GND_2") (pintype "power_in"))
      (node (ref "S4") (pin "2") (pinfunction "GND_2") (pintype "power_in"))
      (node (ref "S5") (pin "2") (pinfunction "GND_2") (pintype "power_in"))
      (node (ref "S6") (pin "2") (pinfunction "GND_2") (pintype "power_in"))
      (node (ref "S7") (pin "2") (pinfunction "GND_2") (pintype "power_in"))
      (node (ref "S8") (pin "2") (pinfunction "GND_2") (pintype "power_in"))
      (node (ref "S9") (pin "2") (pinfunction "GND_2") (pintype "power_in"))
      (node (ref "SG1") (pin "-") (pinfunction "2_-") (pintype "passive"))
      (node (ref "SV2") (pin "3") (pinfunction "3_3") (pintype "passive"))
      (node (ref "SV4") (pin "1") (pinfunction "1_1") (pintype "passive"))
      (node (ref "SW_DEBUG") (pin "3") (pinfunction "S_3") (pintype "passive"))
      (node (ref "SW_DEBUG1") (pin "3") (pinfunction "S_3") (pintype "passive"))
      (node (ref "U$1") (pin "AGND") (pinfunction "AGND_AGND") (pintype "bidirectional"))
      (node (ref "U$1") (pin "GND") (pinfunction "GND_GND") (pintype "bidirectional"))
      (node (ref "U$1") (pin "GND2") (pinfunction "GND2_GND2") (pintype "bidirectional"))
      (node (ref "U$1") (pin "GND3") (pinfunction "GND3_GND3") (pintype "bidirectional"))
      (node (ref "U$2") (pin "19") (pinfunction "VSS_19") (pintype "power_in"))
      (node (ref "U$2") (pin "8") (pinfunction "VSS_2_8") (pintype "power_in"))
      (node (ref "US_EST") (pin "5") (pinfunction "5_5") (pintype "passive"))
      (node (ref "US_NORD") (pin "5") (pinfunction "5_5") (pintype "passive"))
      (node (ref "US_OVEST") (pin "5") (pinfunction "5_5") (pintype "passive"))
      (node (ref "US_SUD") (pin "5") (pinfunction "5_5") (pintype "passive"))
      (node (ref "WEBBECAMMME") (pin "4") (pinfunction "4_4") (pintype "bidirectional"))
    )
    (net (code "61") (name "Net-(D1-K)") (class "Default")
      (node (ref "D1") (pin "1") (pinfunction "K_1") (pintype "bidirectional"))
      (node (ref "IC1") (pin "2") (pinfunction "OUT_2") (pintype "output"))
      (node (ref "U$3") (pin "P$2") (pinfunction "P$2_P$2") (pintype "passive"))
    )
    (net (code "62") (name "Net-(D2-A)") (class "Default")
      (node (ref "D2") (pin "2") (pinfunction "A_2") (pintype "bidirectional"))
      (node (ref "D3") (pin "2") (pinfunction "A_2") (pintype "bidirectional"))
      (node (ref "D4") (pin "2") (pinfunction "A_2") (pintype "bidirectional"))
      (node (ref "R5") (pin "1") (pinfunction "1_1") (pintype "passive"))
      (node (ref "U$3") (pin "P$1") (pinfunction "P$1_P$1") (pintype "passive"))
    )
    (net (code "63") (name "Net-(IC1-FB)") (class "Default")
      (node (ref "IC1") (pin "4") (pinfunction "FB_4") (pintype "input"))
      (node (ref "R4") (pin "2") (pinfunction "2_2") (pintype "passive"))
      (node (ref "R5") (pin "2") (pinfunction "2_2") (pintype "passive"))
    )
    (net (code "64") (name "Net-(J1-PGC)") (class "Default")
      (node (ref "J1") (pin "2") (pinfunction "PGC_2") (pintype "bidirectional"))
      (node (ref "U$2") (pin "27") (pinfunction "RB6//KBI2/PGC_27") (pintype "bidirectional"))
    )
    (net (code "65") (name "Net-(J1-PGD)") (class "Default")
      (node (ref "J1") (pin "3") (pinfunction "PGD_3") (pintype "bidirectional"))
      (node (ref "U$2") (pin "28") (pinfunction "RB7/KBI3/PGD_28") (pintype "bidirectional"))
    )
    (net (code "66") (name "Net-(J1-VPP)") (class "Default")
      (node (ref "J1") (pin "6") (pinfunction "VPP_6") (pintype "bidirectional"))
      (node (ref "R1") (pin "1") (pinfunction "1_1") (pintype "passive"))
      (node (ref "U$2") (pin "1") (pinfunction "~{MCLR/VPP/RE3}_1") (pintype "input"))
    )
    (net (code "67") (name "Net-(LED1-A)") (class "Default")
      (node (ref "LED1") (pin "2") (pinfunction "A_2") (pintype "bidirectional"))
      (node (ref "R2") (pin "2") (pinfunction "2_2") (pintype "passive"))
    )
    (net (code "68") (name "Net-(LED2-K)") (class "Default")
      (node (ref "LED2") (pin "1") (pinfunction "K_1") (pintype "bidirectional"))
      (node (ref "R3") (pin "2") (pinfunction "2_2") (pintype "passive"))
    )
    (net (code "69") (name "Net-(LED3-K)") (class "Default")
      (node (ref "LED3") (pin "1") (pinfunction "K_1") (pintype "bidirectional"))
      (node (ref "R6") (pin "2") (pinfunction "2_2") (pintype "passive"))
    )
    (net (code "70") (name "Net-(LED4-K)") (class "Default")
      (node (ref "LED4") (pin "1") (pinfunction "K_1") (pintype "bidirectional"))
      (node (ref "R7") (pin "2") (pinfunction "2_2") (pintype "passive"))
    )
    (net (code "71") (name "Net-(R2-Pad1)") (class "Default")
      (node (ref "R2") (pin "1") (pinfunction "1_1") (pintype "passive"))
      (node (ref "U$1") (pin "13/SCK") (pinfunction "13/SCK_13/SCK") (pintype "bidirectional"))
    )
    (net (code "72") (name "Net-(S1-VCC)") (class "Default")
      (node (ref "CS2") (pin "1") (pinfunction "1_1") (pintype "passive"))
      (node (ref "RB2") (pin "2") (pinfunction "2_2") (pintype "passive"))
      (node (ref "S1") (pin "3") (pinfunction "VCC_3") (pintype "power_in"))
      (node (ref "S2") (pin "3") (pinfunction "VCC_3") (pintype "power_in"))
      (node (ref "S3") (pin "3") (pinfunction "VCC_3") (pintype "power_in"))
      (node (ref "S4") (pin "3") (pinfunction "VCC_3") (pintype "power_in"))
    )
    (net (code "73") (name "Net-(S5-VCC)") (class "Default")
      (node (ref "CS1") (pin "1") (pinfunction "1_1") (pintype "passive"))
      (node (ref "RB1") (pin "2") (pinfunction "2_2") (pintype "passive"))
      (node (ref "S5") (pin "3") (pinfunction "VCC_3") (pintype "power_in"))
      (node (ref "S6") (pin "3") (pinfunction "VCC_3") (pintype "power_in"))
      (node (ref "S7") (pin "3") (pinfunction "VCC_3") (pintype "power_in"))
      (node (ref "S8") (pin "3") (pinfunction "VCC_3") (pintype "power_in"))
    )
    (net (code "74") (name "Net-(S10-VCC)") (class "Default")
      (node (ref "CS3") (pin "1") (pinfunction "1_1") (pintype "passive"))
      (node (ref "RB3") (pin "2") (pinfunction "2_2") (pintype "passive"))
      (node (ref "S10") (pin "3") (pinfunction "VCC_3") (pintype "power_in"))
      (node (ref "S11") (pin "3") (pinfunction "VCC_3") (pintype "power_in"))
      (node (ref "S12") (pin "3") (pinfunction "VCC_3") (pintype "power_in"))
      (node (ref "S9") (pin "3") (pinfunction "VCC_3") (pintype "power_in"))
    )
    (net (code "75") (name "Net-(S_ELETTR.-P)") (class "Default")
      (node (ref "BAT_12V1") (pin "1") (pinfunction "1_1") (pintype "passive"))
      (node (ref "C10") (pin "1") (pinfunction "1_1") (pintype "bidirectional"))
      (node (ref "C11") (pin "1") (pinfunction "1_1") (pintype "bidirectional"))
      (node (ref "S_ELETTR.") (pin "2") (pinfunction "P_2") (pintype "passive"))
      (node (ref "S_ELETTR.") (pin "3") (pinfunction "S_3") (pintype "passive"))
      (node (ref "S_MOTORI") (pin "2") (pinfunction "P_2") (pintype "passive"))
      (node (ref "S_MOTORI") (pin "3") (pinfunction "S_3") (pintype "passive"))
    )
    (net (code "76") (name "unconnected-(12C_AUX-Pad1)") (class "Default")
      (node (ref "12C_AUX") (pin "1") (pinfunction "1_1") (pintype "passive"))
    )
    (net (code "77") (name "unconnected-(BLUTUTTU-Pad1)") (class "Default")
      (node (ref "BLUTUTTU") (pin "1") (pinfunction "1_1") (pintype "passive"))
    )
    (net (code "78") (name "unconnected-(BLUTUTTU-Pad6)") (class "Default")
      (node (ref "BLUTUTTU") (pin "6") (pinfunction "6_6") (pintype "passive"))
    )
    (net (code "79") (name "unconnected-(J1-PGM-Pad1)") (class "Default")
      (node (ref "J1") (pin "1") (pinfunction "PGM_1") (pintype "bidirectional"))
    )
    (net (code "80") (name "unconnected-(SV1-Pad1)") (class "Default")
      (node (ref "SV1") (pin "1") (pinfunction "1_1") (pintype "passive"))
    )
    (net (code "81") (name "unconnected-(SV1-Pad2)") (class "Default")
      (node (ref "SV1") (pin "2") (pinfunction "2_2") (pintype "passive"))
    )
    (net (code "82") (name "unconnected-(SV1-Pad3)") (class "Default")
      (node (ref "SV1") (pin "3") (pinfunction "3_3") (pintype "passive"))
    )
    (net (code "83") (name "unconnected-(SV1-Pad4)") (class "Default")
      (node (ref "SV1") (pin "4") (pinfunction "4_4") (pintype "passive"))
    )
    (net (code "84") (name "unconnected-(SV2-Pad1)") (class "Default")
      (node (ref "SV2") (pin "1") (pinfunction "1_1") (pintype "passive"))
    )
    (net (code "85") (name "unconnected-(SV2-Pad6)") (class "Default")
      (node (ref "SV2") (pin "6") (pinfunction "6_6") (pintype "passive"))
    )
    (net (code "86") (name "unconnected-(U$1-Pad3V3)") (class "Default")
      (node (ref "U$1") (pin "3V3") (pinfunction "3V3_3V3") (pintype "bidirectional"))
    )
    (net (code "87") (name "unconnected-(U$1-Pad3V3_2)") (class "Default")
      (node (ref "U$1") (pin "3V3_2") (pinfunction "3V3_2_3V3_2") (pintype "bidirectional"))
    )
    (net (code "88") (name "unconnected-(U$1-Pad3V3_LO)") (class "Default")
      (node (ref "U$1") (pin "3V3_LO") (pinfunction "3V3_LO_3V3_LO") (pintype "bidirectional"))
    )
    (net (code "89") (name "unconnected-(U$1-PadA10)") (class "Default")
      (node (ref "U$1") (pin "A10") (pinfunction "A10_A10") (pintype "bidirectional"))
    )
    (net (code "90") (name "unconnected-(U$1-PadA11)") (class "Default")
      (node (ref "U$1") (pin "A11") (pinfunction "A11_A11") (pintype "bidirectional"))
    )
    (net (code "91") (name "unconnected-(U$1-PadAREF)") (class "Default")
      (node (ref "U$1") (pin "AREF") (pinfunction "AREF_AREF") (pintype "bidirectional"))
    )
    (net (code "92") (name "unconnected-(U$1-PadPROG)") (class "Default")
      (node (ref "U$1") (pin "PROG") (pinfunction "PROG_PROG") (pintype "bidirectional"))
    )
    (net (code "93") (name "unconnected-(U$1-PadRESET)") (class "Default")
      (node (ref "U$1") (pin "RESET") (pinfunction "RESET_RESET") (pintype "bidirectional"))
    )
    (net (code "94") (name "unconnected-(U$1-PadU5V)") (class "Default")
      (node (ref "U$1") (pin "U5V") (pinfunction "U5V_U5V") (pintype "bidirectional"))
    )
    (net (code "95") (name "unconnected-(U$1-PadUD+)") (class "Default")
      (node (ref "U$1") (pin "UD+") (pinfunction "UD+_UD+") (pintype "bidirectional"))
    )
    (net (code "96") (name "unconnected-(U$1-PadUD-)") (class "Default")
      (node (ref "U$1") (pin "UD-") (pinfunction "UD-_UD-") (pintype "bidirectional"))
    )
    (net (code "97") (name "unconnected-(U$1-PadUGND1)") (class "Default")
      (node (ref "U$1") (pin "UGND1") (pinfunction "UGND1_UGND1") (pintype "bidirectional"))
    )
    (net (code "98") (name "unconnected-(U$1-PadUGND2)") (class "Default")
      (node (ref "U$1") (pin "UGND2") (pinfunction "UGND2_UGND2") (pintype "bidirectional"))
    )
    (net (code "99") (name "unconnected-(U$1-PadVBAT)") (class "Default")
      (node (ref "U$1") (pin "VBAT") (pinfunction "VBAT_VBAT") (pintype "bidirectional"))
    )
    (net (code "100") (name "unconnected-(U$1-PadVUSB)") (class "Default")
      (node (ref "U$1") (pin "VUSB") (pinfunction "VUSB_VUSB") (pintype "bidirectional"))
    )
    (net (code "101") (name "unconnected-(U$2-OSC1{slash}CLKI{slash}RA7-Pad9)") (class "Default")
      (node (ref "U$2") (pin "9") (pinfunction "OSC1/CLKI/RA7_9") (pintype "bidirectional"))
    )
    (net (code "102") (name "unconnected-(U$2-OSC2{slash}CLKO{slash}RA6-Pad10)") (class "Default")
      (node (ref "U$2") (pin "10") (pinfunction "OSC2/CLKO/RA6_10") (pintype "bidirectional"))
    )
    (net (code "103") (name "unconnected-(U$2-RA0{slash}AN0-Pad2)") (class "Default")
      (node (ref "U$2") (pin "2") (pinfunction "RA0/AN0_2") (pintype "bidirectional"))
    )
    (net (code "104") (name "unconnected-(U$2-RA1{slash}AN1-Pad3)") (class "Default")
      (node (ref "U$2") (pin "3") (pinfunction "RA1/AN1_3") (pintype "bidirectional"))
    )
    (net (code "105") (name "unconnected-(U$2-RA2{slash}AN2{slash}VREF-{slash}CVREF-Pad4)") (class "Default")
      (node (ref "U$2") (pin "4") (pinfunction "RA2/AN2/VREF-/CVREF_4") (pintype "bidirectional"))
    )
    (net (code "106") (name "unconnected-(U$2-RA3{slash}AN3{slash}VREF+-Pad5)") (class "Default")
      (node (ref "U$2") (pin "5") (pinfunction "RA3/AN3/VREF+_5") (pintype "bidirectional"))
    )
    (net (code "107") (name "unconnected-(U$2-RA4{slash}T0CKI{slash}C1OUT-Pad6)") (class "Default")
      (node (ref "U$2") (pin "6") (pinfunction "RA4/T0CKI/C1OUT_6") (pintype "bidirectional"))
    )
    (net (code "108") (name "unconnected-(U$2-RA5{slash}AN4{slash}~{SS{slash}HLVDIN{slash}C2OUT}-Pad7)") (class "Default")
      (node (ref "U$2") (pin "7") (pinfunction "RA5/AN4/~{SS/HLVDIN/C2OUT}_7") (pintype "bidirectional"))
    )
    (net (code "109") (name "unconnected-(US_EST-Pad1)") (class "Default")
      (node (ref "US_EST") (pin "1") (pinfunction "1_1") (pintype "passive"))
    )
    (net (code "110") (name "unconnected-(US_NORD-Pad1)") (class "Default")
      (node (ref "US_NORD") (pin "1") (pinfunction "1_1") (pintype "passive"))
    )
    (net (code "111") (name "unconnected-(US_OVEST-Pad1)") (class "Default")
      (node (ref "US_OVEST") (pin "1") (pinfunction "1_1") (pintype "passive"))
    )
    (net (code "112") (name "unconnected-(US_SUD-Pad1)") (class "Default")
      (node (ref "US_SUD") (pin "1") (pinfunction "1_1") (pintype "passive"))
    )
  )
)
